# Connectors_and_USB.net
KiCad netlist of a schematic drawn in Altium Designer
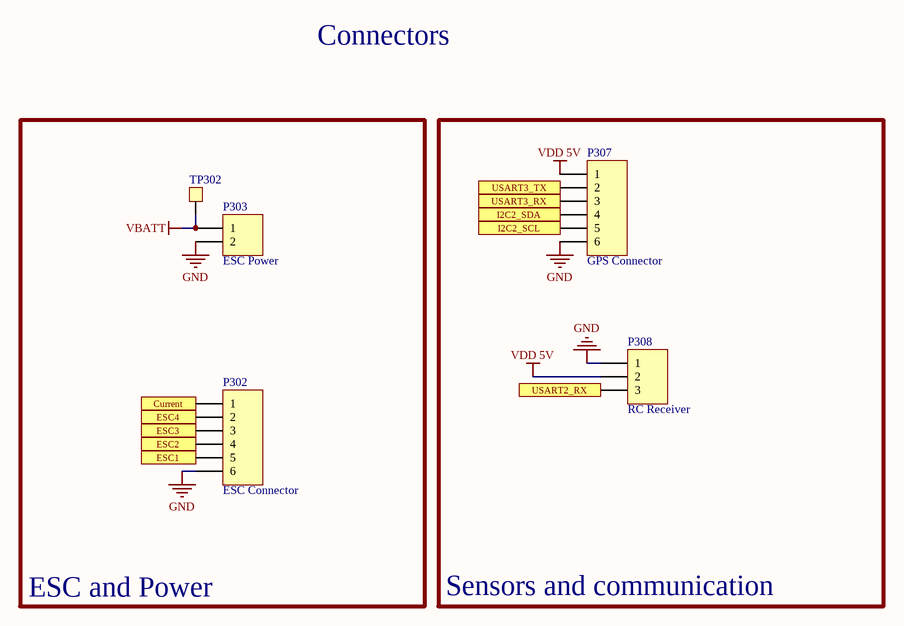
[diagram p0: Connectors and USB.SchDoc]

(export (version "E")
  (design (tool "Eeschema 10.0.6"))
  (components
    (comp (ref "P302")
      (value "ESC Connector")
      (footprint "B6B-XH-A")
      (description "Header, 6-Pin")
      (fields (field (name "PUBLISHER") "Altium Limited"))
      (libsource (lib "Miscellaneous Connectors") (part "Header 6"))
    )
    (comp (ref "P303")
      (value "ESC Power")
      (footprint "HDR1X2")
      (description "Header, 2-Pin")
      (fields (field (name "PUBLISHER") "Altium Limited"))
      (libsource (lib "Miscellaneous Connectors") (part "Header 2"))
    )
    (comp (ref "P307")
      (value "GPS Connector")
      (footprint "B6B-XH-A")
      (description "Header, 6-Pin")
      (fields (field (name "PUBLISHER") "Altium Limited"))
      (libsource (lib "Miscellaneous Connectors") (part "Header 6"))
    )
    (comp (ref "P308")
      (value "RC Receiver")
      (footprint "B3B-XH-A")
      (description "Header, 3-Pin")
      (fields (field (name "PUBLISHER") "Altium Limited"))
      (libsource (lib "Miscellaneous Connectors") (part "Header 3"))
    )
    (comp (ref "TP302")
      (value "Test Point")
      (footprint "Test Point THT 1mm")
      (libsource (lib "FYP_Drone") (part "Test Point"))
    )
  )
  (nets
    (net (code "1") (name "/Current") (class "Default")
      (node (ref "P302") (pin "1") (pinfunction "1_1") (pintype "passive"))
    )
    (net (code "2") (name "/ESC1") (class "Default")
      (node (ref "P302") (pin "5") (pinfunction "5_5") (pintype "passive"))
    )
    (net (code "3") (name "/ESC2") (class "Default")
      (node (ref "P302") (pin "4") (pinfunction "4_4") (pintype "passive"))
    )
    (net (code "4") (name "/ESC3") (class "Default")
      (node (ref "P302") (pin "3") (pinfunction "3_3") (pintype "passive"))
    )
    (net (code "5") (name "/ESC4") (class "Default")
      (node (ref "P302") (pin "2") (pinfunction "2_2") (pintype "passive"))
    )
    (net (code "6") (name "/I2C2_SCL") (class "Default")
      (node (ref "P307") (pin "5") (pinfunction "5_5") (pintype "passive"))
    )
    (net (code "7") (name "/I2C2_SDA") (class "Default")
      (node (ref "P307") (pin "4") (pinfunction "4_4") (pintype "passive"))
    )
    (net (code "8") (name "/USART2_RX") (class "Default")
      (node (ref "P308") (pin "3") (pinfunction "3_3") (pintype "passive"))
    )
    (net (code "9") (name "/USART3_RX") (class "Default")
      (node (ref "P307") (pin "3") (pinfunction "3_3") (pintype "passive"))
    )
    (net (code "10") (name "/USART3_TX") (class "Default")
      (node (ref "P307") (pin "2") (pinfunction "2_2") (pintype "passive"))
    )
    (net (code "11") (name "GND") (class "Default")
      (node (ref "P302") (pin "6") (pinfunction "6_6") (pintype "passive"))
      (node (ref "P303") (pin "2") (pinfunction "2_2") (pintype "passive"))
      (node (ref "P307") (pin "6") (pinfunction "6_6") (pintype "passive"))
      (node (ref "P308") (pin "1") (pinfunction "1_1") (pintype "passive"))
    )
    (net (code "12") (name "VBATT") (class "Default")
      (node (ref "P303") (pin "1") (pinfunction "1_1") (pintype "passive"))
      (node (ref "TP302") (pin "1") (pintype "passive"))
    )
    (net (code "13") (name "VDD 5V") (class "Default")
      (node (ref "P307") (pin "1") (pinfunction "1_1") (pintype "passive"))
      (node (ref "P308") (pin "2") (pinfunction "2_2") (pintype "passive"))
    )
  )
)
